# biosphereMonitor.net
KiCad netlist of a schematic drawn in EAGLE
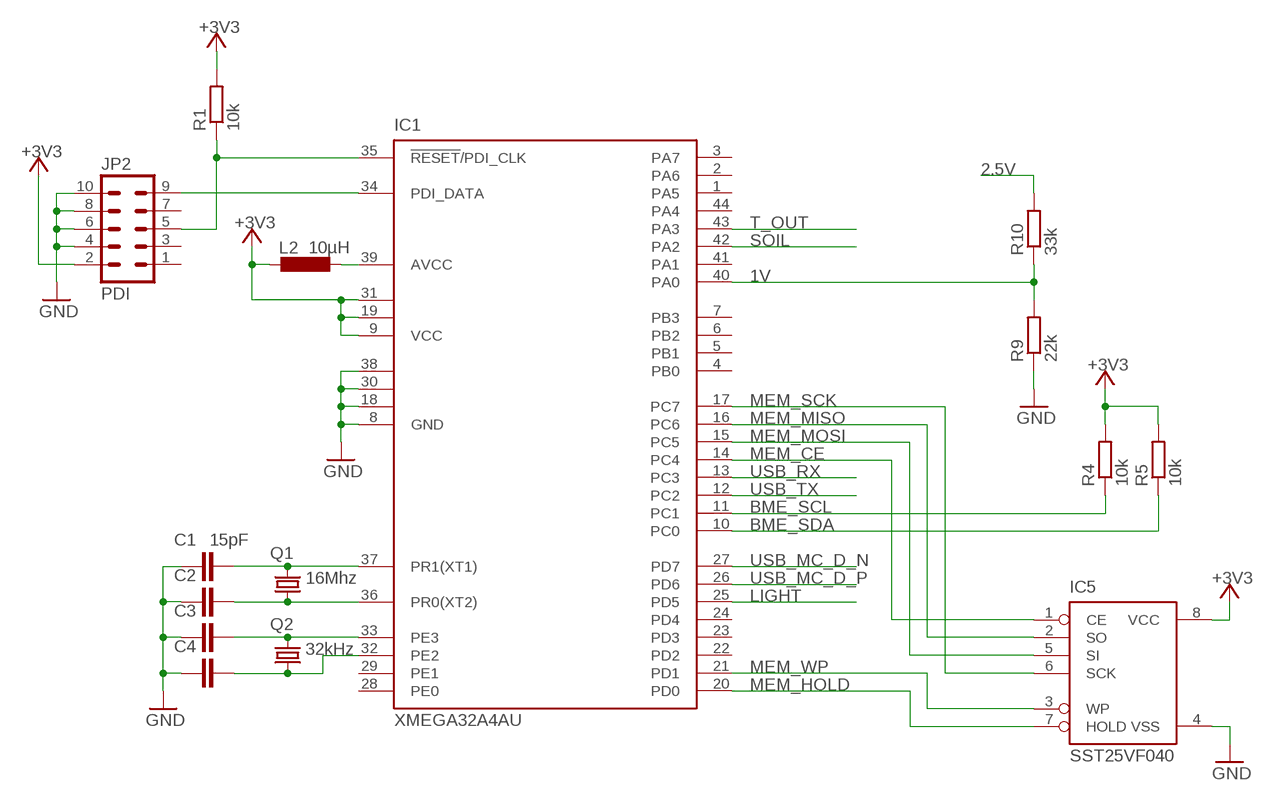
[diagram p0: schematic, sheet 1]
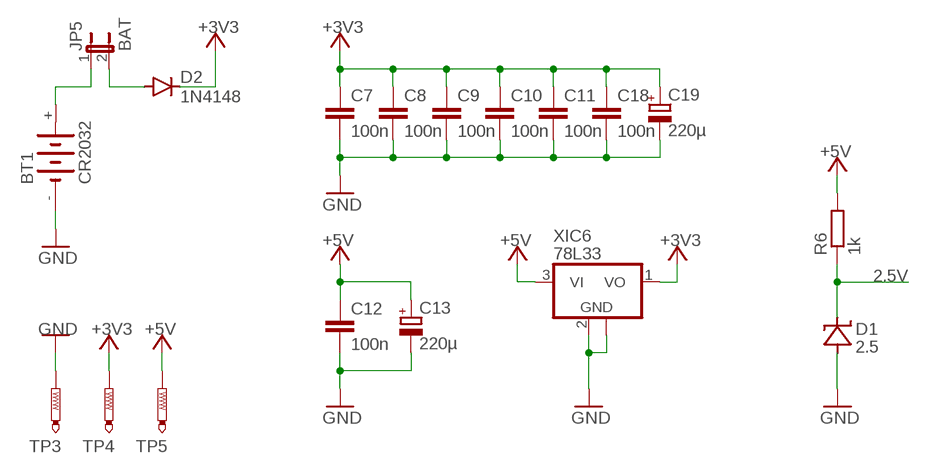
[diagram p1: schematic, sheet 2]
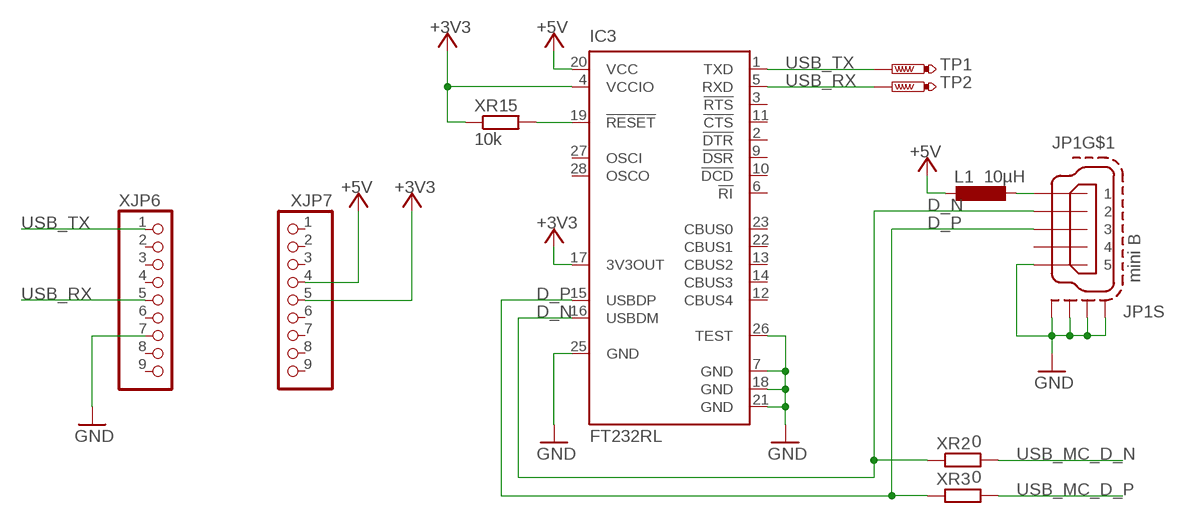
[diagram p2: schematic, sheet 3]
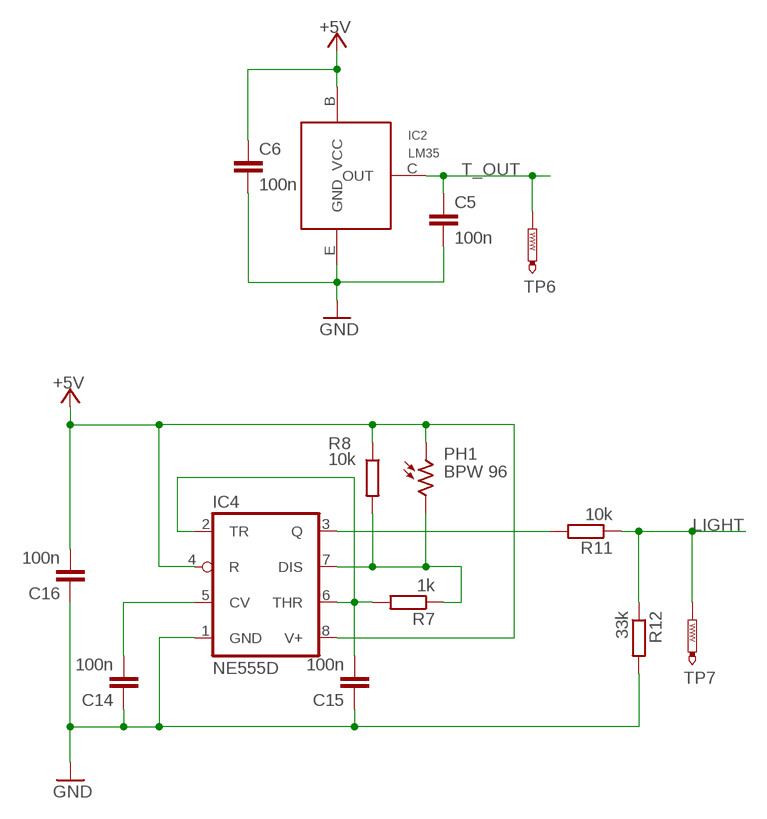
[diagram p3: schematic, sheet 4]
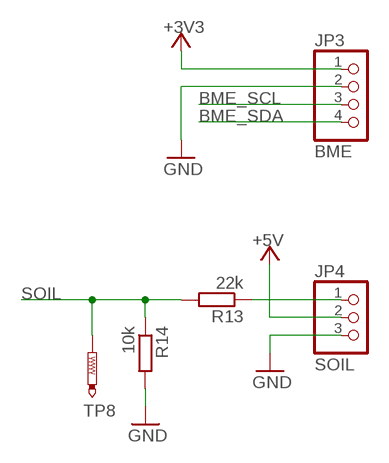
[diagram p4: schematic, sheet 5]

(export (version "E")
  (design (tool "Eeschema 10.0.6"))
  (components
    (comp (ref "BT1")
      (value "CR2032")
      (footprint "eagle-import:CR2032")
      (libsource (lib "eagle-import") (part "CR2032"))
    )
    (comp (ref "C7")
      (value "100n")
      (footprint "eagle-import:C0805")
      (libsource (lib "eagle-import") (part "C-EUC0805"))
    )
    (comp (ref "C8")
      (value "100n")
      (footprint "eagle-import:C0805")
      (libsource (lib "eagle-import") (part "C-EUC0805"))
    )
    (comp (ref "C9")
      (value "100n")
      (footprint "eagle-import:C0805")
      (libsource (lib "eagle-import") (part "C-EUC0805"))
    )
    (comp (ref "C10")
      (value "100n")
      (footprint "eagle-import:C0805")
      (libsource (lib "eagle-import") (part "C-EUC0805"))
    )
    (comp (ref "C11")
      (value "100n")
      (footprint "eagle-import:C0805")
      (libsource (lib "eagle-import") (part "C-EUC0805"))
    )
    (comp (ref "C12")
      (value "100n")
      (footprint "eagle-import:C0805")
      (libsource (lib "eagle-import") (part "C-EUC0805"))
    )
    (comp (ref "C13")
      (value "220µ")
      (footprint "eagle-import:PANASONIC_G")
      (libsource (lib "eagle-import") (part "CPOL-EUG"))
    )
    (comp (ref "C18")
      (value "100n")
      (footprint "eagle-import:C0805")
      (libsource (lib "eagle-import") (part "C-EUC0805"))
    )
    (comp (ref "C19")
      (value "220µ")
      (footprint "eagle-import:PANASONIC_G")
      (libsource (lib "eagle-import") (part "CPOL-EUG"))
    )
    (comp (ref "D1")
      (value "2.5")
      (footprint "eagle-import:SOT23")
      (libsource (lib "eagle-import") (part "LM4040"))
    )
    (comp (ref "D2")
      (value "1N4148")
      (footprint "eagle-import:MINIMELF")
      (libsource (lib "eagle-import") (part "DIODE-MINIMELF"))
    )
    (comp (ref "JP5")
      (value "BAT")
      (footprint "eagle-import:JP1")
      (libsource (lib "eagle-import") (part "JP1E"))
    )
    (comp (ref "R6")
      (value "1k")
      (footprint "eagle-import:R0805")
      (libsource (lib "eagle-import") (part "R-EU_R0805"))
    )
    (comp (ref "TP3")
      (value "PTR1B2,54")
      (footprint "eagle-import:B2,54")
      (libsource (lib "eagle-import") (part "PTR1B2,54"))
    )
    (comp (ref "TP4")
      (value "PTR1B2,54")
      (footprint "eagle-import:B2,54")
      (libsource (lib "eagle-import") (part "PTR1B2,54"))
    )
    (comp (ref "TP5")
      (value "PTR1B2,54")
      (footprint "eagle-import:B2,54")
      (libsource (lib "eagle-import") (part "PTR1B2,54"))
    )
    (comp (ref "XIC6")
      (value "78L33")
      (footprint "eagle-import:SOT89")
      (libsource (lib "eagle-import") (part "78LF05"))
    )
    (comp (ref "C5")
      (value "100n")
      (footprint "eagle-import:C0805")
      (libsource (lib "eagle-import") (part "C-EUC0805"))
    )
    (comp (ref "C6")
      (value "100n")
      (footprint "eagle-import:C0805")
      (libsource (lib "eagle-import") (part "C-EUC0805"))
    )
    (comp (ref "C14")
      (value "100n")
      (footprint "eagle-import:C0805")
      (libsource (lib "eagle-import") (part "C-EUC0805"))
    )
    (comp (ref "C15")
      (value "100n")
      (footprint "eagle-import:C0805")
      (libsource (lib "eagle-import") (part "C-EUC0805"))
    )
    (comp (ref "C16")
      (value "100n")
      (footprint "eagle-import:C0805")
      (libsource (lib "eagle-import") (part "C-EUC0805"))
    )
    (comp (ref "IC2")
      (value "LM35")
      (footprint "eagle-import:TO92-BCE")
      (libsource (lib "eagle-import") (part "LM35"))
    )
    (comp (ref "IC4")
      (value "NE555D")
      (footprint "eagle-import:SO08")
      (libsource (lib "eagle-import") (part "555DNE"))
    )
    (comp (ref "PH1")
      (value "BPW 96")
      (footprint "eagle-import:T0-46-A10XX")
      (libsource (lib "eagle-import") (part "A1050_13"))
    )
    (comp (ref "R7")
      (value "1k")
      (footprint "eagle-import:R0805")
      (libsource (lib "eagle-import") (part "R-EU_R0805"))
    )
    (comp (ref "R8")
      (value "10k")
      (footprint "eagle-import:R0805")
      (libsource (lib "eagle-import") (part "R-EU_R0805"))
    )
    (comp (ref "R11")
      (value "10k")
      (footprint "eagle-import:R0805")
      (libsource (lib "eagle-import") (part "R-EU_R0805"))
    )
    (comp (ref "R12")
      (value "33k")
      (footprint "eagle-import:R0805")
      (libsource (lib "eagle-import") (part "R-EU_R0805"))
    )
    (comp (ref "TP6")
      (value "PTR1B2,54")
      (footprint "eagle-import:B2,54")
      (libsource (lib "eagle-import") (part "PTR1B2,54"))
    )
    (comp (ref "TP7")
      (value "PTR1B2,54")
      (footprint "eagle-import:B2,54")
      (libsource (lib "eagle-import") (part "PTR1B2,54"))
    )
    (comp (ref "C1")
      (value "15pF")
      (footprint "eagle-import:C0805")
      (libsource (lib "eagle-import") (part "C-EUC0805"))
    )
    (comp (ref "C2")
      (value "15pF")
      (footprint "eagle-import:C0805")
      (libsource (lib "eagle-import") (part "C-EUC0805"))
    )
    (comp (ref "C3")
      (value "15pF")
      (footprint "eagle-import:C0805")
      (libsource (lib "eagle-import") (part "C-EUC0805"))
    )
    (comp (ref "C4")
      (value "15pF")
      (footprint "eagle-import:C0805")
      (libsource (lib "eagle-import") (part "C-EUC0805"))
    )
    (comp (ref "IC1")
      (value "XMEGA32A4AU")
      (footprint "eagle-import:TQFP44")
      (libsource (lib "eagle-import") (part "XMEGA16A4A"))
    )
    (comp (ref "IC5")
      (value "SST25VF040")
      (footprint "eagle-import:SO08-208")
      (libsource (lib "eagle-import") (part "SST25VF040SO08W"))
    )
    (comp (ref "JP2")
      (value "PDI")
      (footprint "eagle-import:ML10L")
      (libsource (lib "eagle-import") (part "ML10L"))
    )
    (comp (ref "L2")
      (value "10µH")
      (footprint "eagle-import:L2012C")
      (libsource (lib "eagle-import") (part "L-EUL2012C"))
    )
    (comp (ref "Q1")
      (value "16Mhz")
      (footprint "eagle-import:SM49")
      (libsource (lib "eagle-import") (part "CRYSTALSM49"))
    )
    (comp (ref "Q2")
      (value "32kHz")
      (footprint "eagle-import:MS1V")
      (libsource (lib "eagle-import") (part "MQ_CRYSTALMS1V"))
    )
    (comp (ref "R1")
      (value "10k")
      (footprint "eagle-import:R0805")
      (libsource (lib "eagle-import") (part "R-EU_R0805"))
    )
    (comp (ref "R4")
      (value "10k")
      (footprint "eagle-import:R0805")
      (libsource (lib "eagle-import") (part "R-EU_R0805"))
    )
    (comp (ref "R5")
      (value "10k")
      (footprint "eagle-import:R0805")
      (libsource (lib "eagle-import") (part "R-EU_R0805"))
    )
    (comp (ref "R9")
      (value "22k")
      (footprint "eagle-import:R0805")
      (libsource (lib "eagle-import") (part "R-EU_R0805"))
    )
    (comp (ref "R10")
      (value "33k")
      (footprint "eagle-import:R0805")
      (libsource (lib "eagle-import") (part "R-EU_R0805"))
    )
    (comp (ref "IC3")
      (value "FT232RL")
      (footprint "eagle-import:SSOP28")
      (libsource (lib "eagle-import") (part "FT232RL"))
    )
    (comp (ref "JP1")
      (value "mini B")
      (footprint "eagle-import:32005-301")
      (libsource (lib "eagle-import") (part "MINI-USB-SCHIELD-32005-301"))
    )
    (comp (ref "L1")
      (value "10µH")
      (footprint "eagle-import:L2012C")
      (libsource (lib "eagle-import") (part "L-EUL2012C"))
    )
    (comp (ref "TP1")
      (value "PTR1B2,54")
      (footprint "eagle-import:B2,54")
      (libsource (lib "eagle-import") (part "PTR1B2,54"))
    )
    (comp (ref "TP2")
      (value "PTR1B2,54")
      (footprint "eagle-import:B2,54")
      (libsource (lib "eagle-import") (part "PTR1B2,54"))
    )
    (comp (ref "XJP6")
      (value "PINHD-1X9")
      (footprint "eagle-import:1X09")
      (libsource (lib "eagle-import") (part "PINHD-1X9"))
    )
    (comp (ref "XJP7")
      (value "PINHD-1X9")
      (footprint "eagle-import:1X09")
      (libsource (lib "eagle-import") (part "PINHD-1X9"))
    )
    (comp (ref "XR2")
      (value "0")
      (footprint "eagle-import:R0805")
      (libsource (lib "eagle-import") (part "R-EU_R0805"))
    )
    (comp (ref "XR3")
      (value "0")
      (footprint "eagle-import:R0805")
      (libsource (lib "eagle-import") (part "R-EU_R0805"))
    )
    (comp (ref "XR15")
      (value "10k")
      (footprint "eagle-import:R0805")
      (libsource (lib "eagle-import") (part "R-EU_R0805"))
    )
    (comp (ref "JP3")
      (value "BME")
      (footprint "eagle-import:1X04")
      (libsource (lib "eagle-import") (part "PINHD-1X4"))
    )
    (comp (ref "JP4")
      (value "SOIL")
      (footprint "eagle-import:1X03")
      (libsource (lib "eagle-import") (part "PINHD-1X3"))
    )
    (comp (ref "R13")
      (value "22k")
      (footprint "eagle-import:R0805")
      (libsource (lib "eagle-import") (part "R-EU_R0805"))
    )
    (comp (ref "R14")
      (value "10k")
      (footprint "eagle-import:R0805")
      (libsource (lib "eagle-import") (part "R-EU_R0805"))
    )
    (comp (ref "TP8")
      (value "PTR1B2,54")
      (footprint "eagle-import:B2,54")
      (libsource (lib "eagle-import") (part "PTR1B2,54"))
    )
  )
  (nets
    (net (code "1") (name "+3V3") (class "Default")
      (node (ref "C10") (pin "2") (pinfunction "2_2") (pintype "passive"))
      (node (ref "C11") (pin "2") (pinfunction "2_2") (pintype "passive"))
      (node (ref "C18") (pin "2") (pinfunction "2_2") (pintype "passive"))
      (node (ref "C19") (pin "+") (pinfunction "+_+") (pintype "passive"))
      (node (ref "C7") (pin "2") (pinfunction "2_2") (pintype "passive"))
      (node (ref "C8") (pin "2") (pinfunction "2_2") (pintype "passive"))
      (node (ref "C9") (pin "2") (pinfunction "2_2") (pintype "passive"))
      (node (ref "D2") (pin "C") (pinfunction "C_C") (pintype "passive"))
      (node (ref "IC1") (pin "19") (pinfunction "VCC1_19") (pintype "power_in"))
      (node (ref "IC1") (pin "31") (pinfunction "VCC2_31") (pintype "power_in"))
      (node (ref "IC1") (pin "9") (pinfunction "VCC_9") (pintype "power_in"))
      (node (ref "IC3") (pin "17") (pinfunction "3V3OUT_17") (pintype "power_in"))
      (node (ref "IC3") (pin "4") (pinfunction "VCCIO_4") (pintype "power_in"))
      (node (ref "IC5") (pin "8") (pinfunction "VCC_8") (pintype "power_in"))
      (node (ref "JP2") (pin "2") (pinfunction "2_2") (pintype "passive"))
      (node (ref "JP3") (pin "1") (pinfunction "1_1") (pintype "passive"))
      (node (ref "L2") (pin "1") (pinfunction "1_1") (pintype "passive"))
      (node (ref "R1") (pin "2") (pinfunction "2_2") (pintype "passive"))
      (node (ref "R4") (pin "2") (pinfunction "2_2") (pintype "passive"))
      (node (ref "R5") (pin "2") (pinfunction "2_2") (pintype "passive"))
      (node (ref "TP4") (pin "TP") (pinfunction "TP_TP") (pintype "input"))
      (node (ref "XIC6") (pin "1") (pinfunction "VO_1") (pintype "passive"))
      (node (ref "XJP7") (pin "5") (pinfunction "5_5") (pintype "passive"))
      (node (ref "XR15") (pin "1") (pinfunction "1_1") (pintype "passive"))
    )
    (net (code "2") (name "+5V") (class "Default")
      (node (ref "C12") (pin "2") (pinfunction "2_2") (pintype "passive"))
      (node (ref "C13") (pin "+") (pinfunction "+_+") (pintype "passive"))
      (node (ref "C16") (pin "1") (pinfunction "1_1") (pintype "passive"))
      (node (ref "C6") (pin "2") (pinfunction "2_2") (pintype "passive"))
      (node (ref "IC2") (pin "B") (pinfunction "VCC_B") (pintype "power_in"))
      (node (ref "IC3") (pin "20") (pinfunction "VCC_20") (pintype "power_in"))
      (node (ref "IC4") (pin "4") (pinfunction "R_4") (pintype "input"))
      (node (ref "IC4") (pin "8") (pinfunction "V+_8") (pintype "power_in"))
      (node (ref "JP4") (pin "2") (pinfunction "2_2") (pintype "passive"))
      (node (ref "L1") (pin "1") (pinfunction "1_1") (pintype "passive"))
      (node (ref "PH1") (pin "1") (pinfunction "1_1") (pintype "passive"))
      (node (ref "R6") (pin "2") (pinfunction "2_2") (pintype "passive"))
      (node (ref "R8") (pin "1") (pinfunction "1_1") (pintype "passive"))
      (node (ref "TP5") (pin "TP") (pinfunction "TP_TP") (pintype "input"))
      (node (ref "XIC6") (pin "3") (pinfunction "VI_3") (pintype "input"))
      (node (ref "XJP7") (pin "4") (pinfunction "4_4") (pintype "passive"))
    )
    (net (code "3") (name "1V") (class "Default")
      (node (ref "IC1") (pin "40") (pinfunction "PA0_40") (pintype "bidirectional"))
      (node (ref "R10") (pin "1") (pinfunction "1_1") (pintype "passive"))
      (node (ref "R9") (pin "2") (pinfunction "2_2") (pintype "passive"))
    )
    (net (code "4") (name "2.5V") (class "Default")
      (node (ref "D1") (pin "1") (pinfunction "C_1") (pintype "passive"))
      (node (ref "R10") (pin "2") (pinfunction "2_2") (pintype "passive"))
      (node (ref "R6") (pin "1") (pinfunction "1_1") (pintype "passive"))
    )
    (net (code "5") (name "BME_SCL") (class "Default")
      (node (ref "IC1") (pin "11") (pinfunction "PC1_11") (pintype "bidirectional"))
      (node (ref "JP3") (pin "3") (pinfunction "3_3") (pintype "passive"))
      (node (ref "R4") (pin "1") (pinfunction "1_1") (pintype "passive"))
    )
    (net (code "6") (name "BME_SDA") (class "Default")
      (node (ref "IC1") (pin "10") (pinfunction "PC0_10") (pintype "bidirectional"))
      (node (ref "JP3") (pin "4") (pinfunction "4_4") (pintype "passive"))
      (node (ref "R5") (pin "1") (pinfunction "1_1") (pintype "passive"))
    )
    (net (code "7") (name "D_N") (class "Default")
      (node (ref "IC3") (pin "16") (pinfunction "USBDM_16") (pintype "bidirectional"))
      (node (ref "JP1") (pin "2") (pinfunction "2_2") (pintype "passive"))
      (node (ref "XR2") (pin "1") (pinfunction "1_1") (pintype "passive"))
    )
    (net (code "8") (name "D_P") (class "Default")
      (node (ref "IC3") (pin "15") (pinfunction "USBDP_15") (pintype "bidirectional"))
      (node (ref "JP1") (pin "3") (pinfunction "3_3") (pintype "passive"))
      (node (ref "XR3") (pin "1") (pinfunction "1_1") (pintype "passive"))
    )
    (net (code "9") (name "GND") (class "Default")
      (node (ref "BT1") (pin "-") (pinfunction "-_-") (pintype "passive"))
      (node (ref "C1") (pin "1") (pinfunction "1_1") (pintype "passive"))
      (node (ref "C10") (pin "1") (pinfunction "1_1") (pintype "passive"))
      (node (ref "C11") (pin "1") (pinfunction "1_1") (pintype "passive"))
      (node (ref "C12") (pin "1") (pinfunction "1_1") (pintype "passive"))
      (node (ref "C13") (pin "-") (pinfunction "-_-") (pintype "passive"))
      (node (ref "C14") (pin "2") (pinfunction "2_2") (pintype "passive"))
      (node (ref "C15") (pin "2") (pinfunction "2_2") (pintype "passive"))
      (node (ref "C16") (pin "2") (pinfunction "2_2") (pintype "passive"))
      (node (ref "C18") (pin "1") (pinfunction "1_1") (pintype "passive"))
      (node (ref "C19") (pin "-") (pinfunction "-_-") (pintype "passive"))
      (node (ref "C2") (pin "1") (pinfunction "1_1") (pintype "passive"))
      (node (ref "C3") (pin "1") (pinfunction "1_1") (pintype "passive"))
      (node (ref "C4") (pin "1") (pinfunction "1_1") (pintype "passive"))
      (node (ref "C5") (pin "1") (pinfunction "1_1") (pintype "passive"))
      (node (ref "C6") (pin "1") (pinfunction "1_1") (pintype "passive"))
      (node (ref "C7") (pin "1") (pinfunction "1_1") (pintype "passive"))
      (node (ref "C8") (pin "1") (pinfunction "1_1") (pintype "passive"))
      (node (ref "C9") (pin "1") (pinfunction "1_1") (pintype "passive"))
      (node (ref "D1") (pin "2") (pinfunction "A_2") (pintype "passive"))
      (node (ref "IC1") (pin "18") (pinfunction "GND1_18") (pintype "power_in"))
      (node (ref "IC1") (pin "30") (pinfunction "GND2_30") (pintype "power_in"))
      (node (ref "IC1") (pin "38") (pinfunction "GND3_38") (pintype "power_in"))
      (node (ref "IC1") (pin "8") (pinfunction "GND_8") (pintype "power_in"))
      (node (ref "IC2") (pin "E") (pinfunction "GND_E") (pintype "power_in"))
      (node (ref "IC3") (pin "18") (pinfunction "GND_18") (pintype "power_in"))
      (node (ref "IC3") (pin "21") (pinfunction "GND_21") (pintype "power_in"))
      (node (ref "IC3") (pin "25") (pinfunction "GND_25") (pintype "power_in"))
      (node (ref "IC3") (pin "26") (pinfunction "TEST_26") (pintype "input"))
      (node (ref "IC3") (pin "7") (pinfunction "GND_7") (pintype "power_in"))
      (node (ref "IC4") (pin "1") (pinfunction "GND_1") (pintype "power_in"))
      (node (ref "IC5") (pin "4") (pinfunction "VSS_4") (pintype "power_in"))
      (node (ref "JP1") (pin "5") (pinfunction "5_5") (pintype "passive"))
      (node (ref "JP1") (pin "M1") (pinfunction "S1_M1") (pintype "passive"))
      (node (ref "JP1") (pin "M2") (pinfunction "S2_M2") (pintype "passive"))
      (node (ref "JP1") (pin "M3") (pinfunction "S3_M3") (pintype "passive"))
      (node (ref "JP1") (pin "M4") (pinfunction "S4_M4") (pintype "passive"))
      (node (ref "JP2") (pin "10") (pinfunction "10_10") (pintype "passive"))
      (node (ref "JP2") (pin "4") (pinfunction "4_4") (pintype "passive"))
      (node (ref "JP2") (pin "6") (pinfunction "6_6") (pintype "passive"))
      (node (ref "JP2") (pin "8") (pinfunction "8_8") (pintype "passive"))
      (node (ref "JP3") (pin "2") (pinfunction "2_2") (pintype "passive"))
      (node (ref "JP4") (pin "3") (pinfunction "3_3") (pintype "passive"))
      (node (ref "R12") (pin "2") (pinfunction "2_2") (pintype "passive"))
      (node (ref "R14") (pin "2") (pinfunction "2_2") (pintype "passive"))
      (node (ref "R9") (pin "1") (pinfunction "1_1") (pintype "passive"))
      (node (ref "TP3") (pin "TP") (pinfunction "TP_TP") (pintype "input"))
      (node (ref "XIC6") (pin "2") (pinfunction "GND_2") (pintype "passive"))
      (node (ref "XIC6") (pin "2@1") (pinfunction "GND_2@1") (pintype "passive"))
      (node (ref "XJP6") (pin "7") (pinfunction "7_7") (pintype "passive"))
    )
    (net (code "10") (name "LIGHT") (class "Default")
      (node (ref "IC1") (pin "25") (pinfunction "PD5_25") (pintype "bidirectional"))
      (node (ref "R11") (pin "1") (pinfunction "1_1") (pintype "passive"))
      (node (ref "R12") (pin "1") (pinfunction "1_1") (pintype "passive"))
      (node (ref "TP7") (pin "TP") (pinfunction "TP_TP") (pintype "input"))
    )
    (net (code "11") (name "MEM_CE") (class "Default")
      (node (ref "IC1") (pin "14") (pinfunction "PC4_14") (pintype "bidirectional"))
      (node (ref "IC5") (pin "1") (pinfunction "CE_1") (pintype "input"))
    )
    (net (code "12") (name "MEM_HOLD") (class "Default")
      (node (ref "IC1") (pin "20") (pinfunction "PD0_20") (pintype "bidirectional"))
      (node (ref "IC5") (pin "7") (pinfunction "HOLD_7") (pintype "input"))
    )
    (net (code "13") (name "MEM_MISO") (class "Default")
      (node (ref "IC1") (pin "16") (pinfunction "PC6_16") (pintype "bidirectional"))
      (node (ref "IC5") (pin "2") (pinfunction "SO_2") (pintype "output"))
    )
    (net (code "14") (name "MEM_MOSI") (class "Default")
      (node (ref "IC1") (pin "15") (pinfunction "PC5_15") (pintype "bidirectional"))
      (node (ref "IC5") (pin "5") (pinfunction "SI_5") (pintype "input"))
    )
    (net (code "15") (name "MEM_SCK") (class "Default")
      (node (ref "IC1") (pin "17") (pinfunction "PC7_17") (pintype "bidirectional"))
      (node (ref "IC5") (pin "6") (pinfunction "SCK_6") (pintype "input"))
    )
    (net (code "16") (name "MEM_WP") (class "Default")
      (node (ref "IC1") (pin "21") (pinfunction "PD1_21") (pintype "bidirectional"))
      (node (ref "IC5") (pin "3") (pinfunction "WP_3") (pintype "input"))
    )
    (net (code "17") (name "Net-(BT1-Pad+)") (class "Default")
      (node (ref "BT1") (pin "+") (pinfunction "+_+") (pintype "passive"))
      (node (ref "JP5") (pin "1") (pinfunction "1_1") (pintype "passive"))
    )
    (net (code "18") (name "Net-(D2-PadA)") (class "Default")
      (node (ref "D2") (pin "A") (pinfunction "A_A") (pintype "passive"))
      (node (ref "JP5") (pin "2") (pinfunction "2_2") (pintype "passive"))
    )
    (net (code "19") (name "Net-(IC1-AVCC)") (class "Default")
      (node (ref "IC1") (pin "39") (pinfunction "AVCC_39") (pintype "power_in"))
      (node (ref "L2") (pin "2") (pinfunction "2_2") (pintype "passive"))
    )
    (net (code "20") (name "Net-(IC1-PDI_DATA)") (class "Default")
      (node (ref "IC1") (pin "34") (pinfunction "PDI_DATA_34") (pintype "bidirectional"))
      (node (ref "JP2") (pin "9") (pinfunction "9_9") (pintype "passive"))
    )
    (net (code "21") (name "Net-(IC1-PE2)") (class "Default")
      (node (ref "C4") (pin "2") (pinfunction "2_2") (pintype "passive"))
      (node (ref "IC1") (pin "32") (pinfunction "PE2_32") (pintype "bidirectional"))
      (node (ref "Q2") (pin "Q2") (pinfunction "2_Q2") (pintype "passive"))
    )
    (net (code "22") (name "Net-(IC1-PE3)") (class "Default")
      (node (ref "C3") (pin "2") (pinfunction "2_2") (pintype "passive"))
      (node (ref "IC1") (pin "33") (pinfunction "PE3_33") (pintype "bidirectional"))
      (node (ref "Q2") (pin "Q1") (pinfunction "1_Q1") (pintype "passive"))
    )
    (net (code "23") (name "Net-(IC1-PR0(XT2))") (class "Default")
      (node (ref "C2") (pin "2") (pinfunction "2_2") (pintype "passive"))
      (node (ref "IC1") (pin "36") (pinfunction "PR0(XT2)_36") (pintype "bidirectional"))
      (node (ref "Q1") (pin "1") (pinfunction "1_1") (pintype "passive"))
    )
    (net (code "24") (name "Net-(IC1-PR1(XT1))") (class "Default")
      (node (ref "C1") (pin "2") (pinfunction "2_2") (pintype "passive"))
      (node (ref "IC1") (pin "37") (pinfunction "PR1(XT1)_37") (pintype "bidirectional"))
      (node (ref "Q1") (pin "2") (pinfunction "2_2") (pintype "passive"))
    )
    (net (code "25") (name "Net-(IC1-~{RESET}{slash}PDI_CLK)") (class "Default")
      (node (ref "IC1") (pin "35") (pinfunction "~{RESET}/PDI_CLK_35") (pintype "bidirectional"))
      (node (ref "JP2") (pin "5") (pinfunction "5_5") (pintype "passive"))
      (node (ref "R1") (pin "1") (pinfunction "1_1") (pintype "passive"))
    )
    (net (code "26") (name "Net-(IC3-~{RESET})") (class "Default")
      (node (ref "IC3") (pin "19") (pinfunction "~{RESET}_19") (pintype "input"))
      (node (ref "XR15") (pin "2") (pinfunction "2_2") (pintype "passive"))
    )
    (net (code "27") (name "Net-(IC4-CV)") (class "Default")
      (node (ref "C14") (pin "1") (pinfunction "1_1") (pintype "passive"))
      (node (ref "IC4") (pin "5") (pinfunction "CV_5") (pintype "input"))
    )
    (net (code "28") (name "Net-(IC4-DIS)") (class "Default")
      (node (ref "IC4") (pin "7") (pinfunction "DIS_7") (pintype "input"))
      (node (ref "PH1") (pin "2") (pinfunction "2_2") (pintype "passive"))
      (node (ref "R7") (pin "1") (pinfunction "1_1") (pintype "passive"))
      (node (ref "R8") (pin "2") (pinfunction "2_2") (pintype "passive"))
    )
    (net (code "29") (name "Net-(IC4-Q)") (class "Default")
      (node (ref "IC4") (pin "3") (pinfunction "Q_3") (pintype "output"))
      (node (ref "R11") (pin "2") (pinfunction "2_2") (pintype "passive"))
    )
    (net (code "30") (name "Net-(IC4-THR)") (class "Default")
      (node (ref "C15") (pin "1") (pinfunction "1_1") (pintype "passive"))
      (node (ref "IC4") (pin "2") (pinfunction "TR_2") (pintype "input"))
      (node (ref "IC4") (pin "6") (pinfunction "THR_6") (pintype "input"))
      (node (ref "R7") (pin "2") (pinfunction "2_2") (pintype "passive"))
    )
    (net (code "31") (name "Net-(JP1-Pad1)") (class "Default")
      (node (ref "JP1") (pin "1") (pinfunction "1_1") (pintype "passive"))
      (node (ref "L1") (pin "2") (pinfunction "2_2") (pintype "passive"))
    )
    (net (code "32") (name "Net-(JP4-Pad1)") (class "Default")
      (node (ref "JP4") (pin "1") (pinfunction "1_1") (pintype "passive"))
      (node (ref "R13") (pin "1") (pinfunction "1_1") (pintype "passive"))
    )
    (net (code "33") (name "SOIL") (class "Default")
      (node (ref "IC1") (pin "42") (pinfunction "PA2_42") (pintype "bidirectional"))
      (node (ref "R13") (pin "2") (pinfunction "2_2") (pintype "passive"))
      (node (ref "R14") (pin "1") (pinfunction "1_1") (pintype "passive"))
      (node (ref "TP8") (pin "TP") (pinfunction "TP_TP") (pintype "input"))
    )
    (net (code "34") (name "T_OUT") (class "Default")
      (node (ref "C5") (pin "2") (pinfunction "2_2") (pintype "passive"))
      (node (ref "IC1") (pin "43") (pinfunction "PA3_43") (pintype "bidirectional"))
      (node (ref "IC2") (pin "C") (pinfunction "OUT_C") (pintype "output"))
      (node (ref "TP6") (pin "TP") (pinfunction "TP_TP") (pintype "input"))
    )
    (net (code "35") (name "USB_MC_D_N") (class "Default")
      (node (ref "IC1") (pin "27") (pinfunction "PD7_27") (pintype "bidirectional"))
      (node (ref "XR2") (pin "2") (pinfunction "2_2") (pintype "passive"))
    )
    (net (code "36") (name "USB_MC_D_P") (class "Default")
      (node (ref "IC1") (pin "26") (pinfunction "PD6_26") (pintype "bidirectional"))
      (node (ref "XR3") (pin "2") (pinfunction "2_2") (pintype "passive"))
    )
    (net (code "37") (name "USB_RX") (class "Default")
      (node (ref "IC1") (pin "13") (pinfunction "PC3_13") (pintype "bidirectional"))
      (node (ref "IC3") (pin "5") (pinfunction "RXD_5") (pintype "input"))
      (node (ref "TP2") (pin "TP") (pinfunction "TP_TP") (pintype "input"))
      (node (ref "XJP6") (pin "5") (pinfunction "5_5") (pintype "passive"))
    )
    (net (code "38") (name "USB_TX") (class "Default")
      (node (ref "IC1") (pin "12") (pinfunction "PC2_12") (pintype "bidirectional"))
      (node (ref "IC3") (pin "1") (pinfunction "TXD_1") (pintype "output"))
      (node (ref "TP1") (pin "TP") (pinfunction "TP_TP") (pintype "input"))
      (node (ref "XJP6") (pin "1") (pinfunction "1_1") (pintype "passive"))
    )
    (net (code "39") (name "unconnected-(IC1-PA1-Pad41)") (class "Default")
      (node (ref "IC1") (pin "41") (pinfunction "PA1_41") (pintype "bidirectional"))
    )
    (net (code "40") (name "unconnected-(IC1-PA4-Pad44)") (class "Default")
      (node (ref "IC1") (pin "44") (pinfunction "PA4_44") (pintype "bidirectional"))
    )
    (net (code "41") (name "unconnected-(IC1-PA5-Pad1)") (class "Default")
      (node (ref "IC1") (pin "1") (pinfunction "PA5_1") (pintype "bidirectional"))
    )
    (net (code "42") (name "unconnected-(IC1-PA6-Pad2)") (class "Default")
      (node (ref "IC1") (pin "2") (pinfunction "PA6_2") (pintype "bidirectional"))
    )
    (net (code "43") (name "unconnected-(IC1-PA7-Pad3)") (class "Default")
      (node (ref "IC1") (pin "3") (pinfunction "PA7_3") (pintype "bidirectional"))
    )
    (net (code "44") (name "unconnected-(IC1-PB0-Pad4)") (class "Default")
      (node (ref "IC1") (pin "4") (pinfunction "PB0_4") (pintype "bidirectional"))
    )
    (net (code "45") (name "unconnected-(IC1-PB1-Pad5)") (class "Default")
      (node (ref "IC1") (pin "5") (pinfunction "PB1_5") (pintype "bidirectional"))
    )
    (net (code "46") (name "unconnected-(IC1-PB2-Pad6)") (class "Default")
      (node (ref "IC1") (pin "6") (pinfunction "PB2_6") (pintype "bidirectional"))
    )
    (net (code "47") (name "unconnected-(IC1-PB3-Pad7)") (class "Default")
      (node (ref "IC1") (pin "7") (pinfunction "PB3_7") (pintype "bidirectional"))
    )
    (net (code "48") (name "unconnected-(IC1-PD2-Pad22)") (class "Default")
      (node (ref "IC1") (pin "22") (pinfunction "PD2_22") (pintype "bidirectional"))
    )
    (net (code "49") (name "unconnected-(IC1-PD3-Pad23)") (class "Default")
      (node (ref "IC1") (pin "23") (pinfunction "PD3_23") (pintype "bidirectional"))
    )
    (net (code "50") (name "unconnected-(IC1-PD4-Pad24)") (class "Default")
      (node (ref "IC1") (pin "24") (pinfunction "PD4_24") (pintype "bidirectional"))
    )
    (net (code "51") (name "unconnected-(IC1-PE0-Pad28)") (class "Default")
      (node (ref "IC1") (pin "28") (pinfunction "PE0_28") (pintype "bidirectional"))
    )
    (net (code "52") (name "unconnected-(IC1-PE1-Pad29)") (class "Default")
      (node (ref "IC1") (pin "29") (pinfunction "PE1_29") (pintype "bidirectional"))
    )
    (net (code "53") (name "unconnected-(IC3-CBUS0-Pad23)") (class "Default")
      (node (ref "IC3") (pin "23") (pinfunction "CBUS0_23") (pintype "bidirectional"))
    )
    (net (code "54") (name "unconnected-(IC3-CBUS1-Pad22)") (class "Default")
      (node (ref "IC3") (pin "22") (pinfunction "CBUS1_22") (pintype "bidirectional"))
    )
    (net (code "55") (name "unconnected-(IC3-CBUS2-Pad13)") (class "Default")
      (node (ref "IC3") (pin "13") (pinfunction "CBUS2_13") (pintype "bidirectional"))
    )
    (net (code "56") (name "unconnected-(IC3-CBUS3-Pad14)") (class "Default")
      (node (ref "IC3") (pin "14") (pinfunction "CBUS3_14") (pintype "bidirectional"))
    )
    (net (code "57") (name "unconnected-(IC3-CBUS4-Pad12)") (class "Default")
      (node (ref "IC3") (pin "12") (pinfunction "CBUS4_12") (pintype "bidirectional"))
    )
    (net (code "58") (name "unconnected-(IC3-OSCI-Pad27)") (class "Default")
      (node (ref "IC3") (pin "27") (pinfunction "OSCI_27") (pintype "input"))
    )
    (net (code "59") (name "unconnected-(IC3-OSCO-Pad28)") (class "Default")
      (node (ref "IC3") (pin "28") (pinfunction "OSCO_28") (pintype "output"))
    )
    (net (code "60") (name "unconnected-(IC3-~{CTS}-Pad11)") (class "Default")
      (node (ref "IC3") (pin "11") (pinfunction "~{CTS}_11") (pintype "bidirectional"))
    )
    (net (code "61") (name "unconnected-(IC3-~{DCD}-Pad10)") (class "Default")
      (node (ref "IC3") (pin "10") (pinfunction "~{DCD}_10") (pintype "bidirectional"))
    )
    (net (code "62") (name "unconnected-(IC3-~{DSR}-Pad9)") (class "Default")
      (node (ref "IC3") (pin "9") (pinfunction "~{DSR}_9") (pintype "bidirectional"))
    )
    (net (code "63") (name "unconnected-(IC3-~{DTR}-Pad2)") (class "Default")
      (node (ref "IC3") (pin "2") (pinfunction "~{DTR}_2") (pintype "output"))
    )
    (net (code "64") (name "unconnected-(IC3-~{RI}-Pad6)") (class "Default")
      (node (ref "IC3") (pin "6") (pinfunction "~{RI}_6") (pintype "bidirectional"))
    )
    (net (code "65") (name "unconnected-(IC3-~{RTS}-Pad3)") (class "Default")
      (node (ref "IC3") (pin "3") (pinfunction "~{RTS}_3") (pintype "output"))
    )
    (net (code "66") (name "unconnected-(JP1-Pad4)") (class "Default")
      (node (ref "JP1") (pin "4") (pinfunction "4_4") (pintype "passive"))
    )
    (net (code "67") (name "unconnected-(JP2-Pad1)") (class "Default")
      (node (ref "JP2") (pin "1") (pinfunction "1_1") (pintype "passive"))
    )
    (net (code "68") (name "unconnected-(JP2-Pad3)") (class "Default")
      (node (ref "JP2") (pin "3") (pinfunction "3_3") (pintype "passive"))
    )
    (net (code "69") (name "unconnected-(JP2-Pad7)") (class "Default")
      (node (ref "JP2") (pin "7") (pinfunction "7_7") (pintype "passive"))
    )
    (net (code "70") (name "unconnected-(XJP6-Pad2)") (class "Default")
      (node (ref "XJP6") (pin "2") (pinfunction "2_2") (pintype "passive"))
    )
    (net (code "71") (name "unconnected-(XJP6-Pad3)") (class "Default")
      (node (ref "XJP6") (pin "3") (pinfunction "3_3") (pintype "passive"))
    )
    (net (code "72") (name "unconnected-(XJP6-Pad4)") (class "Default")
      (node (ref "XJP6") (pin "4") (pinfunction "4_4") (pintype "passive"))
    )
    (net (code "73") (name "unconnected-(XJP6-Pad6)") (class "Default")
      (node (ref "XJP6") (pin "6") (pinfunction "6_6") (pintype "passive"))
    )
    (net (code "74") (name "unconnected-(XJP6-Pad8)") (class "Default")
      (node (ref "XJP6") (pin "8") (pinfunction "8_8") (pintype "passive"))
    )
    (net (code "75") (name "unconnected-(XJP6-Pad9)") (class "Default")
      (node (ref "XJP6") (pin "9") (pinfunction "9_9") (pintype "passive"))
    )
    (net (code "76") (name "unconnected-(XJP7-Pad1)") (class "Default")
      (node (ref "XJP7") (pin "1") (pinfunction "1_1") (pintype "passive"))
    )
    (net (code "77") (name "unconnected-(XJP7-Pad2)") (class "Default")
      (node (ref "XJP7") (pin "2") (pinfunction "2_2") (pintype "passive"))
    )
    (net (code "78") (name "unconnected-(XJP7-Pad3)") (class "Default")
      (node (ref "XJP7") (pin "3") (pinfunction "3_3") (pintype "passive"))
    )
    (net (code "79") (name "unconnected-(XJP7-Pad6)") (class "Default")
      (node (ref "XJP7") (pin "6") (pinfunction "6_6") (pintype "passive"))
    )
    (net (code "80") (name "unconnected-(XJP7-Pad7)") (class "Default")
      (node (ref "XJP7") (pin "7") (pinfunction "7_7") (pintype "passive"))
    )
    (net (code "81") (name "unconnected-(XJP7-Pad8)") (class "Default")
      (node (ref "XJP7") (pin "8") (pinfunction "8_8") (pintype "passive"))
    )
    (net (code "82") (name "unconnected-(XJP7-Pad9)") (class "Default")
      (node (ref "XJP7") (pin "9") (pinfunction "9_9") (pintype "passive"))
    )
  )
)
